# Microcontroller.net
KiCad netlist of a schematic drawn in Altium Designer
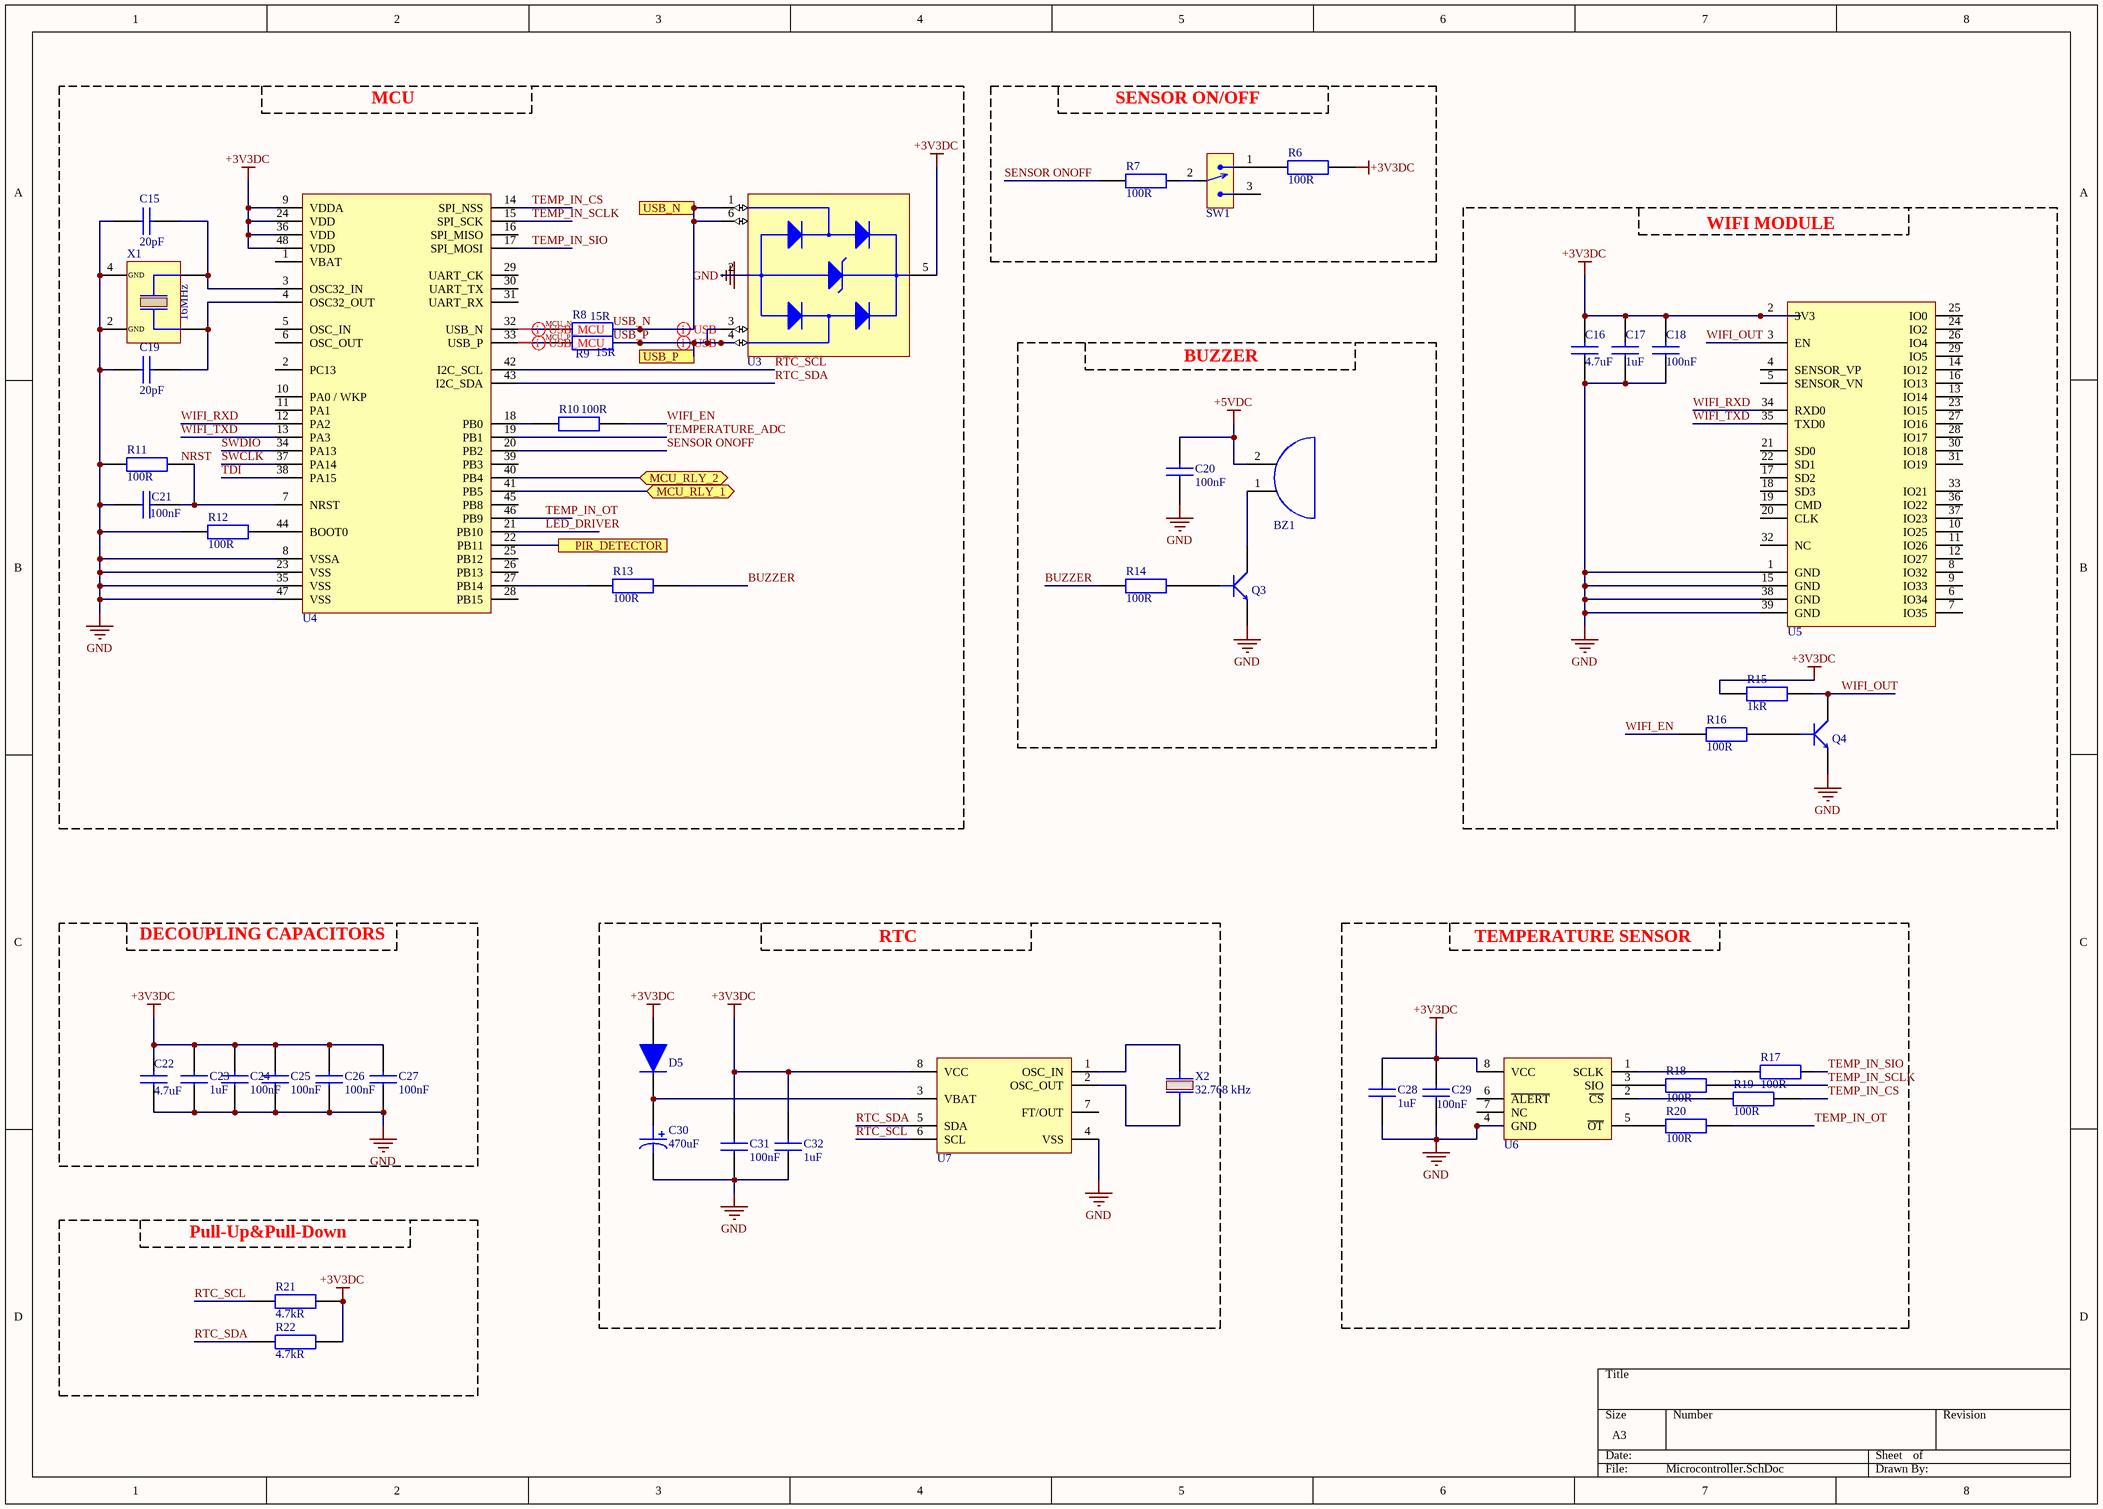
[diagram p0: Microcontroller.SchDoc]

(export (version "E")
  (design (tool "Eeschema 10.0.6"))
  (components
    (comp (ref "BZ1")
      (value "CMI-9605IC-0580T")
      (footprint "CMI-9605IC")
      (description "Buzzers Indicator, Internally Driven Magnetic 5V 30mA 2.7kHz 80dB @ 5V, 10cm Through Hole PC Pins")
      (fields (field (name "MANUFACTURER") "CUI Devices") (field (name "DESIGNED BY") "BERK"))
      (libsource (lib "UDEMY_Library") (part "CMI-9605IC-0580T"))
    )
    (comp (ref "C15")
      (value "CL10C200JB8NNNC")
      (footprint "CAP_0603")
      (description "CAP CER 20pF %5 0603 SMD")
      (fields
        (field (name "MANUFACTURER") "Samsung")
        (field (name "TOLERANCE") "5%")
        (field (name "CAPACITANCE") "20pF")
        (field (name "DESIGNED BY") "BERK")
      )
      (libsource (lib "UDEMY_Library") (part "CAP CER 20pF 0603"))
    )
    (comp (ref "C16")
      (value "CL21A475KAQNNNE")
      (footprint "CAP_0805")
      (description "CAP CER 4.7uF %10 0805")
      (fields
        (field (name "MANUFACTURER") "Samsung")
        (field (name "TOLERANCE") "10%")
        (field (name "CAPACITANCE") "4.7uF")
        (field (name "DESIGNED BY") "BERK")
      )
      (libsource (lib "UDEMY_Library") (part "CAP CER 4.7uF 0805"))
    )
    (comp (ref "C17")
      (value "CL21B105KBFNNNE")
      (footprint "CAP_0805")
      (description "CAP CER 1uF %10 0805")
      (fields
        (field (name "MANUFACTURER") "Samsung")
        (field (name "TOLERANCE") "10%")
        (field (name "CAPACITANCE") "1uF")
        (field (name "DESIGNED BY") "BERK")
      )
      (libsource (lib "UDEMY_Library") (part "CAP CER 1uF 0805"))
    )
    (comp (ref "C18")
      (value "CL21B104KBCNNNC")
      (footprint "CAP_0805")
      (description "CAP CER 100nF %10 0805")
      (fields
        (field (name "MANUFACTURER") "Samsung")
        (field (name "TOLERANCE") "10%")
        (field (name "CAPACITANCE") "100nF")
        (field (name "DESIGNED BY") "BERK")
      )
      (libsource (lib "UDEMY_Library") (part "CAP CER 100nF 0805"))
    )
    (comp (ref "C19")
      (value "CL10C200JB8NNNC")
      (footprint "CAP_0603")
      (description "CAP CER 20pF %5 0603 SMD")
      (fields
        (field (name "MANUFACTURER") "Samsung")
        (field (name "TOLERANCE") "5%")
        (field (name "CAPACITANCE") "20pF")
        (field (name "DESIGNED BY") "BERK")
      )
      (libsource (lib "UDEMY_Library") (part "CAP CER 20pF 0603"))
    )
    (comp (ref "C20")
      (value "CL21B104KBCNNNC")
      (footprint "CAP_0805")
      (description "CAP CER 100nF %10 0805")
      (fields
        (field (name "MANUFACTURER") "Samsung")
        (field (name "TOLERANCE") "10%")
        (field (name "CAPACITANCE") "100nF")
        (field (name "DESIGNED BY") "BERK")
      )
      (libsource (lib "UDEMY_Library") (part "CAP CER 100nF 0805"))
    )
    (comp (ref "C21")
      (value "C0603C104K5RACTU")
      (footprint "CAP_0603")
      (description "CAP CER 100nF %10 0603 SMD")
      (fields
        (field (name "MANUFACTURER") "KEMET")
        (field (name "TOLERANCE") "10%")
        (field (name "CAPACITANCE") "100nF")
        (field (name "DESIGNED BY") "BERK")
      )
      (libsource (lib "UDEMY_Library") (part "CAP CER 100nF 0603"))
    )
    (comp (ref "C22")
      (value "CL21A475KAQNNNE")
      (footprint "CAP_0805")
      (description "CAP CER 4.7uF %10 0805")
      (fields
        (field (name "MANUFACTURER") "Samsung")
        (field (name "TOLERANCE") "10%")
        (field (name "CAPACITANCE") "4.7uF")
        (field (name "DESIGNED BY") "BERK")
      )
      (libsource (lib "UDEMY_Library") (part "CAP CER 4.7uF 0805"))
    )
    (comp (ref "C23")
      (value "CL21B105KBFNNNE")
      (footprint "CAP_0805")
      (description "CAP CER 1uF %10 0805")
      (fields
        (field (name "MANUFACTURER") "Samsung")
        (field (name "TOLERANCE") "10%")
        (field (name "CAPACITANCE") "1uF")
        (field (name "DESIGNED BY") "BERK")
      )
      (libsource (lib "UDEMY_Library") (part "CAP CER 1uF 0805"))
    )
    (comp (ref "C24")
      (value "CL21B104KBCNNNC")
      (footprint "CAP_0805")
      (description "CAP CER 100nF %10 0805")
      (fields
        (field (name "MANUFACTURER") "Samsung")
        (field (name "TOLERANCE") "10%")
        (field (name "CAPACITANCE") "100nF")
        (field (name "DESIGNED BY") "BERK")
      )
      (libsource (lib "UDEMY_Library") (part "CAP CER 100nF 0805"))
    )
    (comp (ref "C25")
      (value "CL21B104KBCNNNC")
      (footprint "CAP_0805")
      (description "CAP CER 100nF %10 0805")
      (fields
        (field (name "MANUFACTURER") "Samsung")
        (field (name "TOLERANCE") "10%")
        (field (name "CAPACITANCE") "100nF")
        (field (name "DESIGNED BY") "BERK")
      )
      (libsource (lib "UDEMY_Library") (part "CAP CER 100nF 0805"))
    )
    (comp (ref "C26")
      (value "CL21B104KBCNNNC")
      (footprint "CAP_0805")
      (description "CAP CER 100nF %10 0805")
      (fields
        (field (name "MANUFACTURER") "Samsung")
        (field (name "TOLERANCE") "10%")
        (field (name "CAPACITANCE") "100nF")
        (field (name "DESIGNED BY") "BERK")
      )
      (libsource (lib "UDEMY_Library") (part "CAP CER 100nF 0805"))
    )
    (comp (ref "C27")
      (value "CL21B104KBCNNNC")
      (footprint "CAP_0805")
      (description "CAP CER 100nF %10 0805")
      (fields
        (field (name "MANUFACTURER") "Samsung")
        (field (name "TOLERANCE") "10%")
        (field (name "CAPACITANCE") "100nF")
        (field (name "DESIGNED BY") "BERK")
      )
      (libsource (lib "UDEMY_Library") (part "CAP CER 100nF 0805"))
    )
    (comp (ref "C28")
      (value "CL21B105KBFNNNE")
      (footprint "CAP_0805")
      (description "CAP CER 1uF %10 0805")
      (fields
        (field (name "MANUFACTURER") "Samsung")
        (field (name "TOLERANCE") "10%")
        (field (name "CAPACITANCE") "1uF")
        (field (name "DESIGNED BY") "BERK")
      )
      (libsource (lib "UDEMY_Library") (part "CAP CER 1uF 0805"))
    )
    (comp (ref "C29")
      (value "CL21B104KBCNNNC")
      (footprint "CAP_0805")
      (description "CAP CER 100nF %10 0805")
      (fields
        (field (name "MANUFACTURER") "Samsung")
        (field (name "TOLERANCE") "10%")
        (field (name "CAPACITANCE") "100nF")
        (field (name "DESIGNED BY") "BERK")
      )
      (libsource (lib "UDEMY_Library") (part "CAP CER 100nF 0805"))
    )
    (comp (ref "C30")
      (value "ESH477M050AH4AA")
      (footprint "CAP_RADIAL_D10_P5")
      (description "CAP ALU ELEC 470uF 50V RADIAL")
      (fields
        (field (name "MANUFACTURER") "KEMET")
        (field (name "TOLERANCE") "20%")
        (field (name "CAPACITANCE") "470uF")
        (field (name "DESIGNED BY") "BERK")
      )
      (libsource (lib "UDEMY_Library") (part "CAP ALU ELEC 470uF 50V"))
    )
    (comp (ref "C31")
      (value "CL21B104KBCNNNC")
      (footprint "CAP_0805")
      (description "CAP CER 100nF %10 0805")
      (fields
        (field (name "MANUFACTURER") "Samsung")
        (field (name "TOLERANCE") "10%")
        (field (name "CAPACITANCE") "100nF")
        (field (name "DESIGNED BY") "BERK")
      )
      (libsource (lib "UDEMY_Library") (part "CAP CER 100nF 0805"))
    )
    (comp (ref "C32")
      (value "CL21B105KBFNNNE")
      (footprint "CAP_0805")
      (description "CAP CER 1uF %10 0805")
      (fields
        (field (name "MANUFACTURER") "Samsung")
        (field (name "TOLERANCE") "10%")
        (field (name "CAPACITANCE") "1uF")
        (field (name "DESIGNED BY") "BERK")
      )
      (libsource (lib "UDEMY_Library") (part "CAP CER 1uF 0805"))
    )
    (comp (ref "D5")
      (value "1N4148WS")
      (footprint "SOD323F")
      (description "Diode, Single, 75 V, 150 mA, 1 V, 4 ns")
      (fields
        (field (name "MANUFACTURER") "ON Semiconductor / Fairchild")
        (field (name "DESIGNED BY") "BERK")
      )
      (libsource (lib "UDEMY_Library") (part "1N4148WS"))
    )
    (comp (ref "Q3")
      (value "MMBT3904-7-F")
      (footprint "SOT-23F")
      (description "Transistor General Purpose BJT NPN 40 Volt 0.2A Automotive 3-Pin SOT-23")
      (fields (field (name "MANUFACTURER") "Diodes Zetex") (field (name "DESIGNED BY") "BERK"))
      (libsource (lib "UDEMY_Library") (part "MMBT3904-7-F"))
    )
    (comp (ref "Q4")
      (value "MMBT3904-7-F")
      (footprint "SOT-23F")
      (description "Transistor General Purpose BJT NPN 40 Volt 0.2A Automotive 3-Pin SOT-23")
      (fields (field (name "MANUFACTURER") "Diodes Zetex") (field (name "DESIGNED BY") "BERK"))
      (libsource (lib "UDEMY_Library") (part "MMBT3904-7-F"))
    )
    (comp (ref "R6")
      (value "RC0603JR-07100RL")
      (footprint "RES_0603")
      (description "RES 100 %5 OHM 0603 SMD")
      (fields
        (field (name "MANUFACTURER") "Yageo")
        (field (name "TOLERANCE") "5%")
        (field (name "RESISTANCE") "100R")
        (field (name "DESIGNED BY") "BERK")
      )
      (libsource (lib "UDEMY_Library") (part "RES 100 OHM 0603"))
    )
    (comp (ref "R7")
      (value "RC0603JR-07100RL")
      (footprint "RES_0603")
      (description "RES 100 %5 OHM 0603 SMD")
      (fields
        (field (name "MANUFACTURER") "Yageo")
        (field (name "TOLERANCE") "5%")
        (field (name "RESISTANCE") "100R")
        (field (name "DESIGNED BY") "BERK")
      )
      (libsource (lib "UDEMY_Library") (part "RES 100 OHM 0603"))
    )
    (comp (ref "R8")
      (value "RC0603JR-0715RL")
      (footprint "RES_0603")
      (description "RES 15 %5 OHM 0603 SMD")
      (fields
        (field (name "MANUFACTURER") "Yageo")
        (field (name "TOLERANCE") "5%")
        (field (name "RESISTANCE") "15R")
        (field (name "DESIGNED BY") "BERK")
      )
      (libsource (lib "UDEMY_Library") (part "RES 15 OHM 0603"))
    )
    (comp (ref "R9")
      (value "RC0603JR-0715RL")
      (footprint "RES_0603")
      (description "RES 15 %5 OHM 0603 SMD")
      (fields
        (field (name "MANUFACTURER") "Yageo")
        (field (name "TOLERANCE") "5%")
        (field (name "RESISTANCE") "15R")
        (field (name "DESIGNED BY") "BERK")
      )
      (libsource (lib "UDEMY_Library") (part "RES 15 OHM 0603"))
    )
    (comp (ref "R10")
      (value "RC0603JR-07100RL")
      (footprint "RES_0603")
      (description "RES 100 %5 OHM 0603 SMD")
      (fields
        (field (name "MANUFACTURER") "Yageo")
        (field (name "TOLERANCE") "5%")
        (field (name "RESISTANCE") "100R")
        (field (name "DESIGNED BY") "BERK")
      )
      (libsource (lib "UDEMY_Library") (part "RES 100 OHM 0603"))
    )
    (comp (ref "R11")
      (value "RC0603JR-07100RL")
      (footprint "RES_0603")
      (description "RES 100 %5 OHM 0603 SMD")
      (fields
        (field (name "MANUFACTURER") "Yageo")
        (field (name "TOLERANCE") "5%")
        (field (name "RESISTANCE") "100R")
        (field (name "DESIGNED BY") "BERK")
      )
      (libsource (lib "UDEMY_Library") (part "RES 100 OHM 0603"))
    )
    (comp (ref "R12")
      (value "RC0603JR-07100RL")
      (footprint "RES_0603")
      (description "RES 100 %5 OHM 0603 SMD")
      (fields
        (field (name "MANUFACTURER") "Yageo")
        (field (name "TOLERANCE") "5%")
        (field (name "RESISTANCE") "100R")
        (field (name "DESIGNED BY") "BERK")
      )
      (libsource (lib "UDEMY_Library") (part "RES 100 OHM 0603"))
    )
    (comp (ref "R13")
      (value "RC0603JR-07100RL")
      (footprint "RES_0603")
      (description "RES 100 %5 OHM 0603 SMD")
      (fields
        (field (name "MANUFACTURER") "Yageo")
        (field (name "TOLERANCE") "5%")
        (field (name "RESISTANCE") "100R")
        (field (name "DESIGNED BY") "BERK")
      )
      (libsource (lib "UDEMY_Library") (part "RES 100 OHM 0603"))
    )
    (comp (ref "R14")
      (value "RC0603JR-07100RL")
      (footprint "RES_0603")
      (description "RES 100 %5 OHM 0603 SMD")
      (fields
        (field (name "MANUFACTURER") "Yageo")
        (field (name "TOLERANCE") "5%")
        (field (name "RESISTANCE") "100R")
        (field (name "DESIGNED BY") "BERK")
      )
      (libsource (lib "") (part "RES 100 OHM 0603_1"))
    )
    (comp (ref "R15")
      (value "RC0603FR-0710KL")
      (footprint "RES_0603")
      (description "RES 1K %1 OHM 0603 SMD")
      (fields
        (field (name "MANUFACTURER") "Yageo")
        (field (name "MANUFACTURER PART NUMBER") "RC0603JR-071KL")
        (field (name "RESISTANCE") "1kR")
        (field (name "DESIGNED BY") "BERK")
      )
      (libsource (lib "UDEMY_Library") (part "RES 1K OHM 0603"))
    )
    (comp (ref "R16")
      (value "RC0603JR-07100RL")
      (footprint "RES_0603")
      (description "RES 100 %5 OHM 0603 SMD")
      (fields
        (field (name "MANUFACTURER") "Yageo")
        (field (name "TOLERANCE") "5%")
        (field (name "RESISTANCE") "100R")
        (field (name "DESIGNED BY") "BERK")
      )
      (libsource (lib "") (part "RES 100 OHM 0603_1"))
    )
    (comp (ref "R17")
      (value "RC0603JR-07100RL")
      (footprint "RES_0603")
      (description "RES 100 %5 OHM 0603 SMD")
      (fields
        (field (name "MANUFACTURER") "Yageo")
        (field (name "TOLERANCE") "5%")
        (field (name "RESISTANCE") "100R")
        (field (name "DESIGNED BY") "BERK")
      )
      (libsource (lib "UDEMY_Library") (part "RES 100 OHM 0603"))
    )
    (comp (ref "R18")
      (value "RC0603JR-07100RL")
      (footprint "RES_0603")
      (description "RES 100 %5 OHM 0603 SMD")
      (fields
        (field (name "MANUFACTURER") "Yageo")
        (field (name "TOLERANCE") "5%")
        (field (name "RESISTANCE") "100R")
        (field (name "DESIGNED BY") "BERK")
      )
      (libsource (lib "UDEMY_Library") (part "RES 100 OHM 0603"))
    )
    (comp (ref "R19")
      (value "RC0603JR-07100RL")
      (footprint "RES_0603")
      (description "RES 100 %5 OHM 0603 SMD")
      (fields
        (field (name "MANUFACTURER") "Yageo")
        (field (name "TOLERANCE") "5%")
        (field (name "RESISTANCE") "100R")
        (field (name "DESIGNED BY") "BERK")
      )
      (libsource (lib "UDEMY_Library") (part "RES 100 OHM 0603"))
    )
    (comp (ref "R20")
      (value "RC0603JR-07100RL")
      (footprint "RES_0603")
      (description "RES 100 %5 OHM 0603 SMD")
      (fields
        (field (name "MANUFACTURER") "Yageo")
        (field (name "TOLERANCE") "5%")
        (field (name "RESISTANCE") "100R")
        (field (name "DESIGNED BY") "BERK")
      )
      (libsource (lib "") (part "RES 100 OHM 0603_1"))
    )
    (comp (ref "R21")
      (value "RC0603JR-074K7L")
      (footprint "RES_0603")
      (description "RES 4K7 %5 OHM 0603 SMD")
      (fields
        (field (name "MANUFACTURER") "Yageo")
        (field (name "TOLERANCE") "5%")
        (field (name "RESISTANCE") "4.7kR")
        (field (name "DESIGNED BY") "BERK")
      )
      (libsource (lib "UDEMY_Library") (part "RES 4K7 OHM 0603"))
    )
    (comp (ref "R22")
      (value "RC0603JR-074K7L")
      (footprint "RES_0603")
      (description "RES 4K7 %5 OHM 0603 SMD")
      (fields
        (field (name "MANUFACTURER") "Yageo")
        (field (name "TOLERANCE") "5%")
        (field (name "RESISTANCE") "4.7kR")
        (field (name "DESIGNED BY") "BERK")
      )
      (libsource (lib "UDEMY_Library") (part "RES 4K7 OHM 0603"))
    )
    (comp (ref "SW1")
      (value "EG1215AA")
      (footprint "EG1215AA")
      (description "Slide Switch, SPDT, 0.025A, 24V, SMD")
      (fields
        (field (name "MANUFACTURER") "E-Switch")
        (field (name "TOLERANCE") "4.95%")
        (field (name "DESIGNED BY") "BERK")
      )
      (libsource (lib "UDEMY_Library") (part "EG1215AA"))
    )
    (comp (ref "U3")
      (value "USBLC6-2SC6")
      (footprint "SOT23-6L")
      (description "TVS DIODE 5.25V 17V SOT23-6")
      (fields (field (name "MANUFACTURER") "STMicroelectronics") (field (name "DESIGNED BY") "BERK"))
      (libsource (lib "UDEMY_Library") (part "USB PROTECTION"))
    )
    (comp (ref "U4")
      (value "STM32F103C6T6A")
      (footprint "LQFP-48")
      (description "MCU 32-bit STM32F ARM Cortex M3 RISC 32KB Flash 2.5V/3.3V 48-Pin LQFP Tray")
      (fields (field (name "MANUFACTURER") "STMicroelectronics") (field (name "DESIGNED BY") "BERK"))
      (libsource (lib "UDEMY_Library") (part "STM32F103C6T6A"))
    )
    (comp (ref "U5")
      (value "ESP32-WROOM-32")
      (footprint "ESP32-32")
      (description "SMD MODULE, ESP32-D0WDQ6, 32MBIT")
      (fields (field (name "MANUFACTURER") "Espressif Systems") (field (name "DESIGNED BY") "BERK"))
      (libsource (lib "UDEMY_Library") (part "ESP32-WROOM-32"))
    )
    (comp (ref "U6")
      (value "MAX6662")
      (footprint "SOIC8")
      (description "SENSOR TEMPERATURE SPI 8SOIC")
      (fields
        (field (name "MANUFACTURER") "Maxim")
        (field (name "MANUFACTURER PART NUMBER") "MAX6662MSA+")
        (field (name "DESIGNED BY") "BERK")
      )
      (libsource (lib "UDEMY_Library") (part "MAX6662"))
    )
    (comp (ref "U7")
      (value "M41T00M6F")
      (footprint "SOIC8")
      (description "IC RTC CLK/CALENDAR I2C 8-SOIC")
      (fields (field (name "MANUFACTURER") "STMicroelectronics") (field (name "DESIGNED BY") "BERK"))
      (libsource (lib "UDEMY_Library") (part "M41T00M6F"))
    )
    (comp (ref "X1")
      (value "ECS-160-20-30B-TR")
      (footprint "ECS")
      (description "CRYSTAL 16.0000MHZ 20PF SMD")
      (fields
        (field (name "MANUFACTURER") "ECS International")
        (field (name "TOLERANCE") "50ppm")
        (field (name "FREQUENCY") "16MHz")
        (field (name "DESIGNED BY") "BERK")
      )
      (libsource (lib "UDEMY_Library") (part "CRYSTAL 16MHz"))
    )
    (comp (ref "X2")
      (value "ABS05-32.768KHZ-T")
      (footprint "ABS05")
      (description "Crystal, 32.768 kHz, SMD, 1.6mm x 1mm, 12.5 pF, 20 ppm, ABS05 Series")
      (fields
        (field (name "MANUFACTURER") "Abracon")
        (field (name "TOLERANCE") "20ppm")
        (field (name "OPERATING FREQUENCY") "32.768 kHz")
        (field (name "DESIGNED BY") "BERK")
      )
      (libsource (lib "UDEMY_Library") (part "CRYSTAL 32768kHZ"))
    )
  )
  (nets
    (net (code "1") (name "+3V3DC") (class "Default")
      (node (ref "C16") (pin "2") (pinfunction "2_2") (pintype "passive"))
      (node (ref "C17") (pin "2") (pinfunction "2_2") (pintype "passive"))
      (node (ref "C18") (pin "2") (pinfunction "2_2") (pintype "passive"))
      (node (ref "C22") (pin "2") (pinfunction "2_2") (pintype "passive"))
      (node (ref "C23") (pin "2") (pinfunction "2_2") (pintype "passive"))
      (node (ref "C24") (pin "2") (pinfunction "2_2") (pintype "passive"))
      (node (ref "C25") (pin "2") (pinfunction "2_2") (pintype "passive"))
      (node (ref "C26") (pin "2") (pinfunction "2_2") (pintype "passive"))
      (node (ref "C27") (pin "2") (pinfunction "2_2") (pintype "passive"))
      (node (ref "C28") (pin "2") (pinfunction "2_2") (pintype "passive"))
      (node (ref "C29") (pin "2") (pinfunction "2_2") (pintype "passive"))
      (node (ref "C31") (pin "2") (pinfunction "2_2") (pintype "passive"))
      (node (ref "C32") (pin "2") (pinfunction "2_2") (pintype "passive"))
      (node (ref "D5") (pin "2") (pinfunction "2_2") (pintype "power_in"))
      (node (ref "R15") (pin "1") (pinfunction "1_1") (pintype "passive"))
      (node (ref "R21") (pin "2") (pinfunction "2_2") (pintype "passive"))
      (node (ref "R22") (pin "2") (pinfunction "2_2") (pintype "passive"))
      (node (ref "R6") (pin "2") (pinfunction "2_2") (pintype "passive"))
      (node (ref "U3") (pin "5") (pinfunction "VBUS_5") (pintype "power_in"))
      (node (ref "U4") (pin "24") (pinfunction "VDD_24") (pintype "passive"))
      (node (ref "U4") (pin "36") (pinfunction "VDD_36") (pintype "passive"))
      (node (ref "U4") (pin "48") (pinfunction "VDD_48") (pintype "passive"))
      (node (ref "U4") (pin "9") (pinfunction "VDDA_9") (pintype "passive"))
      (node (ref "U5") (pin "2") (pinfunction "3V3_2") (pintype "passive"))
      (node (ref "U6") (pin "8") (pinfunction "VCC_8") (pintype "passive"))
      (node (ref "U7") (pin "8") (pinfunction "VCC_8") (pintype "passive"))
    )
    (net (code "2") (name "+5VDC") (class "Default")
      (node (ref "BZ1") (pin "2") (pinfunction "2_2") (pintype "passive"))
      (node (ref "C20") (pin "2") (pinfunction "2_2") (pintype "passive"))
    )
    (net (code "3") (name "/BUZZER") (class "Default")
      (node (ref "R13") (pin "2") (pinfunction "2_2") (pintype "passive"))
      (node (ref "R14") (pin "2") (pinfunction "2_2") (pintype "passive"))
    )
    (net (code "4") (name "/LED_DRIVER") (class "Default")
      (node (ref "U4") (pin "21") (pinfunction "PB10_21") (pintype "passive"))
    )
    (net (code "5") (name "/MCU_N") (class "Default")
      (node (ref "R8") (pin "1") (pinfunction "1_1") (pintype "passive"))
      (node (ref "U4") (pin "32") (pinfunction "USB_N_32") (pintype "passive"))
    )
    (net (code "6") (name "/MCU_P") (class "Default")
      (node (ref "R9") (pin "1") (pinfunction "1_1") (pintype "passive"))
      (node (ref "U4") (pin "33") (pinfunction "USB_P_33") (pintype "passive"))
    )
    (net (code "7") (name "/MCU_RLY_1") (class "Default")
      (node (ref "U4") (pin "41") (pinfunction "PB5_41") (pintype "passive"))
    )
    (net (code "8") (name "/MCU_RLY_2") (class "Default")
      (node (ref "U4") (pin "40") (pinfunction "PB4_40") (pintype "passive"))
    )
    (net (code "10") (name "/PIR_DETECTOR") (class "Default")
      (node (ref "U4") (pin "22") (pinfunction "PB11_22") (pintype "passive"))
    )
    (net (code "11") (name "/RTC_SCL") (class "Default")
      (node (ref "R21") (pin "1") (pinfunction "1_1") (pintype "passive"))
      (node (ref "U4") (pin "42") (pinfunction "I2C_SCL_42") (pintype "passive"))
      (node (ref "U7") (pin "6") (pinfunction "SCL_6") (pintype "passive"))
    )
    (net (code "12") (name "/RTC_SDA") (class "Default")
      (node (ref "R22") (pin "1") (pinfunction "1_1") (pintype "passive"))
      (node (ref "U4") (pin "43") (pinfunction "I2C_SDA_43") (pintype "passive"))
      (node (ref "U7") (pin "5") (pinfunction "SDA_5") (pintype "passive"))
    )
    (net (code "13") (name "/SENSOR ONOFF") (class "Default")
      (node (ref "R7") (pin "1") (pinfunction "1_1") (pintype "passive"))
      (node (ref "U4") (pin "20") (pinfunction "PB2_20") (pintype "passive"))
    )
    (net (code "14") (name "/SWCLK") (class "Default")
      (node (ref "U4") (pin "37") (pinfunction "PA14_37") (pintype "passive"))
    )
    (net (code "15") (name "/SWDIO") (class "Default")
      (node (ref "U4") (pin "34") (pinfunction "PA13_34") (pintype "passive"))
    )
    (net (code "16") (name "/TDI") (class "Default")
      (node (ref "U4") (pin "38") (pinfunction "PA15_38") (pintype "passive"))
    )
    (net (code "17") (name "/TEMPERATURE_ADC") (class "Default")
      (node (ref "U4") (pin "19") (pinfunction "PB1_19") (pintype "passive"))
    )
    (net (code "18") (name "/TEMP_IN_CS") (class "Default")
      (node (ref "R19") (pin "2") (pinfunction "2_2") (pintype "passive"))
      (node (ref "U4") (pin "14") (pinfunction "SPI_NSS_14") (pintype "passive"))
    )
    (net (code "19") (name "/TEMP_IN_OT") (class "Default")
      (node (ref "R20") (pin "1") (pinfunction "1_1") (pintype "passive"))
      (node (ref "U4") (pin "46") (pinfunction "PB9_46") (pintype "passive"))
    )
    (net (code "20") (name "/TEMP_IN_SCLK") (class "Default")
      (node (ref "R18") (pin "2") (pinfunction "2_2") (pintype "passive"))
      (node (ref "U4") (pin "15") (pinfunction "SPI_SCK_15") (pintype "passive"))
    )
    (net (code "21") (name "/TEMP_IN_SIO") (class "Default")
      (node (ref "R17") (pin "2") (pinfunction "2_2") (pintype "passive"))
      (node (ref "U4") (pin "17") (pinfunction "SPI_MOSI_17") (pintype "passive"))
    )
    (net (code "22") (name "/USB_N") (class "Default")
      (node (ref "R8") (pin "2") (pinfunction "2_2") (pintype "passive"))
      (node (ref "U3") (pin "1") (pinfunction "I/O1_1") (pintype "bidirectional"))
      (node (ref "U3") (pin "6") (pinfunction "I/O1_6") (pintype "bidirectional"))
    )
    (net (code "23") (name "/USB_P") (class "Default")
      (node (ref "R9") (pin "2") (pinfunction "2_2") (pintype "passive"))
      (node (ref "U3") (pin "3") (pinfunction "I/O2_3") (pintype "bidirectional"))
      (node (ref "U3") (pin "4") (pinfunction "I/O2_4") (pintype "bidirectional"))
    )
    (net (code "24") (name "/WIFI_EN") (class "Default")
      (node (ref "R10") (pin "2") (pinfunction "2_2") (pintype "passive"))
      (node (ref "R16") (pin "2") (pinfunction "2_2") (pintype "passive"))
    )
    (net (code "25") (name "/WIFI_OUT") (class "Default")
      (node (ref "Q4") (pin "3") (pinfunction "C_3") (pintype "power_in"))
      (node (ref "R15") (pin "2") (pinfunction "2_2") (pintype "passive"))
      (node (ref "U5") (pin "3") (pinfunction "EN_3") (pintype "passive"))
    )
    (net (code "26") (name "/WIFI_RXD") (class "Default")
      (node (ref "U4") (pin "12") (pinfunction "PA2_12") (pintype "passive"))
      (node (ref "U5") (pin "34") (pinfunction "RXD0_34") (pintype "passive"))
    )
    (net (code "27") (name "/WIFI_TXD") (class "Default")
      (node (ref "U4") (pin "13") (pinfunction "PA3_13") (pintype "passive"))
      (node (ref "U5") (pin "35") (pinfunction "TXD0_35") (pintype "passive"))
    )
    (net (code "28") (name "GND") (class "Default")
      (node (ref "C15") (pin "1") (pinfunction "1_1") (pintype "passive"))
      (node (ref "C16") (pin "1") (pinfunction "1_1") (pintype "passive"))
      (node (ref "C17") (pin "1") (pinfunction "1_1") (pintype "passive"))
      (node (ref "C18") (pin "1") (pinfunction "1_1") (pintype "passive"))
      (node (ref "C19") (pin "1") (pinfunction "1_1") (pintype "passive"))
      (node (ref "C20") (pin "1") (pinfunction "1_1") (pintype "passive"))
      (node (ref "C21") (pin "1") (pinfunction "1_1") (pintype "passive"))
      (node (ref "C22") (pin "1") (pinfunction "1_1") (pintype "passive"))
      (node (ref "C23") (pin "1") (pinfunction "1_1") (pintype "passive"))
      (node (ref "C24") (pin "1") (pinfunction "1_1") (pintype "passive"))
      (node (ref "C25") (pin "1") (pinfunction "1_1") (pintype "passive"))
      (node (ref "C26") (pin "1") (pinfunction "1_1") (pintype "passive"))
      (node (ref "C27") (pin "1") (pinfunction "1_1") (pintype "passive"))
      (node (ref "C28") (pin "1") (pinfunction "1_1") (pintype "passive"))
      (node (ref "C29") (pin "1") (pinfunction "1_1") (pintype "passive"))
      (node (ref "C30") (pin "2") (pinfunction "2_2") (pintype "passive"))
      (node (ref "C31") (pin "1") (pinfunction "1_1") (pintype "passive"))
      (node (ref "C32") (pin "1") (pinfunction "1_1") (pintype "passive"))
      (node (ref "Q3") (pin "2") (pinfunction "E_2") (pintype "power_in"))
      (node (ref "Q4") (pin "2") (pinfunction "E_2") (pintype "power_in"))
      (node (ref "R11") (pin "1") (pinfunction "1_1") (pintype "passive"))
      (node (ref "R12") (pin "1") (pinfunction "1_1") (pintype "passive"))
      (node (ref "U3") (pin "2") (pinfunction "GND_2") (pintype "power_in"))
      (node (ref "U4") (pin "23") (pinfunction "VSS_23") (pintype "passive"))
      (node (ref "U4") (pin "35") (pinfunction "VSS_35") (pintype "passive"))
      (node (ref "U4") (pin "47") (pinfunction "VSS_47") (pintype "passive"))
      (node (ref "U4") (pin "8") (pinfunction "VSSA_8") (pintype "passive"))
      (node (ref "U5") (pin "1") (pinfunction "GND_1") (pintype "passive"))
      (node (ref "U5") (pin "15") (pinfunction "GND_15") (pintype "passive"))
      (node (ref "U5") (pin "38") (pinfunction "GND_38") (pintype "passive"))
      (node (ref "U5") (pin "39") (pinfunction "GND_39") (pintype "passive"))
      (node (ref "U6") (pin "4") (pinfunction "GND_4") (pintype "passive"))
      (node (ref "U7") (pin "4") (pinfunction "VSS_4") (pintype "passive"))
      (node (ref "X1") (pin "2") (pinfunction "GND_2") (pintype "passive"))
      (node (ref "X1") (pin "4") (pinfunction "GND_4") (pintype "passive"))
    )
    (net (code "29") (name "Net-(Q3-B)") (class "Default")
      (node (ref "Q3") (pin "1") (pinfunction "B_1") (pintype "power_in"))
      (node (ref "R14") (pin "1") (pinfunction "1_1") (pintype "passive"))
    )
    (net (code "30") (name "Net-(Q3-C)") (class "Default")
      (node (ref "BZ1") (pin "1") (pinfunction "1_1") (pintype "passive"))
      (node (ref "Q3") (pin "3") (pinfunction "C_3") (pintype "power_in"))
    )
    (net (code "31") (name "Net-(Q4-B)") (class "Default")
      (node (ref "Q4") (pin "1") (pinfunction "B_1") (pintype "power_in"))
      (node (ref "R16") (pin "1") (pinfunction "1_1") (pintype "passive"))
    )
    (net (code "32") (name "Net-(R6-Pad1)") (class "Default")
      (node (ref "R6") (pin "1") (pinfunction "1_1") (pintype "passive"))
      (node (ref "SW1") (pin "1") (pinfunction "1_1") (pintype "passive"))
    )
    (net (code "33") (name "Net-(R7-Pad2)") (class "Default")
      (node (ref "R7") (pin "2") (pinfunction "2_2") (pintype "passive"))
      (node (ref "SW1") (pin "2") (pinfunction "2_2") (pintype "passive"))
    )
    (net (code "34") (name "Net-(U4-BOOT0)") (class "Default")
      (node (ref "R12") (pin "2") (pinfunction "2_2") (pintype "passive"))
      (node (ref "U4") (pin "44") (pinfunction "BOOT0_44") (pintype "passive"))
    )
    (net (code "35") (name "Net-(U4-NRST)") (class "Default")
      (node (ref "C21") (pin "2") (pinfunction "2_2") (pintype "passive"))
      (node (ref "R11") (pin "2") (pinfunction "2_2") (pintype "passive"))
      (node (ref "U4") (pin "7") (pinfunction "NRST_7") (pintype "passive"))
    )
    (net (code "36") (name "Net-(U4-OSC32_IN)") (class "Default")
      (node (ref "C15") (pin "2") (pinfunction "2_2") (pintype "passive"))
      (node (ref "U4") (pin "3") (pinfunction "OSC32_IN_3") (pintype "passive"))
      (node (ref "X1") (pin "3") (pinfunction "3_3") (pintype "passive"))
    )
    (net (code "37") (name "Net-(U4-OSC32_OUT)") (class "Default")
      (node (ref "C19") (pin "2") (pinfunction "2_2") (pintype "passive"))
      (node (ref "U4") (pin "4") (pinfunction "OSC32_OUT_4") (pintype "passive"))
      (node (ref "X1") (pin "1") (pinfunction "1_1") (pintype "passive"))
    )
    (net (code "38") (name "Net-(U4-PB0)") (class "Default")
      (node (ref "R10") (pin "1") (pinfunction "1_1") (pintype "passive"))
      (node (ref "U4") (pin "18") (pinfunction "PB0_18") (pintype "passive"))
    )
    (net (code "39") (name "Net-(U4-PB14)") (class "Default")
      (node (ref "R13") (pin "1") (pinfunction "1_1") (pintype "passive"))
      (node (ref "U4") (pin "27") (pinfunction "PB14_27") (pintype "passive"))
    )
    (net (code "40") (name "Net-(U6-SCLK)") (class "Default")
      (node (ref "R17") (pin "1") (pinfunction "1_1") (pintype "passive"))
      (node (ref "U6") (pin "1") (pinfunction "SCLK_1") (pintype "passive"))
    )
    (net (code "41") (name "Net-(U6-SIO)") (class "Default")
      (node (ref "R18") (pin "1") (pinfunction "1_1") (pintype "passive"))
      (node (ref "U6") (pin "3") (pinfunction "SIO_3") (pintype "passive"))
    )
    (net (code "42") (name "Net-(U6-~{CS})") (class "Default")
      (node (ref "R19") (pin "1") (pinfunction "1_1") (pintype "passive"))
      (node (ref "U6") (pin "2") (pinfunction "~{CS}_2") (pintype "passive"))
    )
    (net (code "43") (name "Net-(U6-~{OT})") (class "Default")
      (node (ref "R20") (pin "2") (pinfunction "2_2") (pintype "passive"))
      (node (ref "U6") (pin "5") (pinfunction "~{OT}_5") (pintype "passive"))
    )
    (net (code "44") (name "Net-(U7-OSC_IN)") (class "Default")
      (node (ref "U7") (pin "1") (pinfunction "OSC_IN_1") (pintype "passive"))
      (node (ref "X2") (pin "2") (pinfunction "2_2") (pintype "passive"))
    )
    (net (code "45") (name "Net-(U7-OSC_OUT)") (class "Default")
      (node (ref "U7") (pin "2") (pinfunction "OSC_OUT_2") (pintype "passive"))
      (node (ref "X2") (pin "1") (pinfunction "1_1") (pintype "passive"))
    )
    (net (code "46") (name "Net-(U7-VBAT)") (class "Default")
      (node (ref "C30") (pin "1") (pinfunction "1_1") (pintype "passive"))
      (node (ref "D5") (pin "1") (pinfunction "1_1") (pintype "power_in"))
      (node (ref "U7") (pin "3") (pinfunction "VBAT_3") (pintype "passive"))
    )
    (net (code "47") (name "unconnected-(SW1-Pad3)") (class "Default")
      (node (ref "SW1") (pin "3") (pinfunction "3_3") (pintype "passive"))
    )
    (net (code "48") (name "unconnected-(U4-OSC_IN-Pad5)") (class "Default")
      (node (ref "U4") (pin "5") (pinfunction "OSC_IN_5") (pintype "passive"))
    )
    (net (code "49") (name "unconnected-(U4-OSC_OUT-Pad6)") (class "Default")
      (node (ref "U4") (pin "6") (pinfunction "OSC_OUT_6") (pintype "passive"))
    )
    (net (code "50") (name "unconnected-(U4-PA0_{slash}_WKP-Pad10)") (class "Default")
      (node (ref "U4") (pin "10") (pinfunction "PA0_/_WKP_10") (pintype "passive"))
    )
    (net (code "51") (name "unconnected-(U4-PA1-Pad11)") (class "Default")
      (node (ref "U4") (pin "11") (pinfunction "PA1_11") (pintype "passive"))
    )
    (net (code "52") (name "unconnected-(U4-PB3-Pad39)") (class "Default")
      (node (ref "U4") (pin "39") (pinfunction "PB3_39") (pintype "passive"))
    )
    (net (code "53") (name "unconnected-(U4-PB8-Pad45)") (class "Default")
      (node (ref "U4") (pin "45") (pinfunction "PB8_45") (pintype "passive"))
    )
    (net (code "54") (name "unconnected-(U4-PB12-Pad25)") (class "Default")
      (node (ref "U4") (pin "25") (pinfunction "PB12_25") (pintype "passive"))
    )
    (net (code "55") (name "unconnected-(U4-PB13-Pad26)") (class "Default")
      (node (ref "U4") (pin "26") (pinfunction "PB13_26") (pintype "passive"))
    )
    (net (code "56") (name "unconnected-(U4-PB15-Pad28)") (class "Default")
      (node (ref "U4") (pin "28") (pinfunction "PB15_28") (pintype "passive"))
    )
    (net (code "57") (name "unconnected-(U4-PC13-Pad2)") (class "Default")
      (node (ref "U4") (pin "2") (pinfunction "PC13_2") (pintype "passive"))
    )
    (net (code "58") (name "unconnected-(U4-SPI_MISO-Pad16)") (class "Default")
      (node (ref "U4") (pin "16") (pinfunction "SPI_MISO_16") (pintype "passive"))
    )
    (net (code "59") (name "unconnected-(U4-UART_CK-Pad29)") (class "Default")
      (node (ref "U4") (pin "29") (pinfunction "UART_CK_29") (pintype "passive"))
    )
    (net (code "60") (name "unconnected-(U4-UART_RX-Pad31)") (class "Default")
      (node (ref "U4") (pin "31") (pinfunction "UART_RX_31") (pintype "passive"))
    )
    (net (code "61") (name "unconnected-(U4-UART_TX-Pad30)") (class "Default")
      (node (ref "U4") (pin "30") (pinfunction "UART_TX_30") (pintype "passive"))
    )
    (net (code "62") (name "unconnected-(U4-VBAT-Pad1)") (class "Default")
      (node (ref "U4") (pin "1") (pinfunction "VBAT_1") (pintype "passive"))
    )
    (net (code "63") (name "unconnected-(U5-CLK-Pad20)") (class "Default")
      (node (ref "U5") (pin "20") (pinfunction "CLK_20") (pintype "passive"))
    )
    (net (code "64") (name "unconnected-(U5-CMD-Pad19)") (class "Default")
      (node (ref "U5") (pin "19") (pinfunction "CMD_19") (pintype "passive"))
    )
    (net (code "65") (name "unconnected-(U5-IO0-Pad25)") (class "Default")
      (node (ref "U5") (pin "25") (pinfunction "IO0_25") (pintype "passive"))
    )
    (net (code "66") (name "unconnected-(U5-IO2-Pad24)") (class "Default")
      (node (ref "U5") (pin "24") (pinfunction "IO2_24") (pintype "passive"))
    )
    (net (code "67") (name "unconnected-(U5-IO4-Pad26)") (class "Default")
      (node (ref "U5") (pin "26") (pinfunction "IO4_26") (pintype "passive"))
    )
    (net (code "68") (name "unconnected-(U5-IO5-Pad29)") (class "Default")
      (node (ref "U5") (pin "29") (pinfunction "IO5_29") (pintype "passive"))
    )
    (net (code "69") (name "unconnected-(U5-IO12-Pad14)") (class "Default")
      (node (ref "U5") (pin "14") (pinfunction "IO12_14") (pintype "passive"))
    )
    (net (code "70") (name "unconnected-(U5-IO13-Pad16)") (class "Default")
      (node (ref "U5") (pin "16") (pinfunction "IO13_16") (pintype "passive"))
    )
    (net (code "71") (name "unconnected-(U5-IO14-Pad13)") (class "Default")
      (node (ref "U5") (pin "13") (pinfunction "IO14_13") (pintype "passive"))
    )
    (net (code "72") (name "unconnected-(U5-IO15-Pad23)") (class "Default")
      (node (ref "U5") (pin "23") (pinfunction "IO15_23") (pintype "passive"))
    )
    (net (code "73") (name "unconnected-(U5-IO16-Pad27)") (class "Default")
      (node (ref "U5") (pin "27") (pinfunction "IO16_27") (pintype "passive"))
    )
    (net (code "74") (name "unconnected-(U5-IO17-Pad28)") (class "Default")
      (node (ref "U5") (pin "28") (pinfunction "IO17_28") (pintype "passive"))
    )
    (net (code "75") (name "unconnected-(U5-IO18-Pad30)") (class "Default")
      (node (ref "U5") (pin "30") (pinfunction "IO18_30") (pintype "passive"))
    )
    (net (code "76") (name "unconnected-(U5-IO19-Pad31)") (class "Default")
      (node (ref "U5") (pin "31") (pinfunction "IO19_31") (pintype "passive"))
    )
    (net (code "77") (name "unconnected-(U5-IO21-Pad33)") (class "Default")
      (node (ref "U5") (pin "33") (pinfunction "IO21_33") (pintype "passive"))
    )
    (net (code "78") (name "unconnected-(U5-IO22-Pad36)") (class "Default")
      (node (ref "U5") (pin "36") (pinfunction "IO22_36") (pintype "passive"))
    )
    (net (code "79") (name "unconnected-(U5-IO23-Pad37)") (class "Default")
      (node (ref "U5") (pin "37") (pinfunction "IO23_37") (pintype "passive"))
    )
    (net (code "80") (name "unconnected-(U5-IO25-Pad10)") (class "Default")
      (node (ref "U5") (pin "10") (pinfunction "IO25_10") (pintype "passive"))
    )
    (net (code "81") (name "unconnected-(U5-IO26-Pad11)") (class "Default")
      (node (ref "U5") (pin "11") (pinfunction "IO26_11") (pintype "passive"))
    )
    (net (code "82") (name "unconnected-(U5-IO27-Pad12)") (class "Default")
      (node (ref "U5") (pin "12") (pinfunction "IO27_12") (pintype "passive"))
    )
    (net (code "83") (name "unconnected-(U5-IO32-Pad8)") (class "Default")
      (node (ref "U5") (pin "8") (pinfunction "IO32_8") (pintype "passive"))
    )
    (net (code "84") (name "unconnected-(U5-IO33-Pad9)") (class "Default")
      (node (ref "U5") (pin "9") (pinfunction "IO33_9") (pintype "passive"))
    )
    (net (code "85") (name "unconnected-(U5-IO34-Pad6)") (class "Default")
      (node (ref "U5") (pin "6") (pinfunction "IO34_6") (pintype "passive"))
    )
    (net (code "86") (name "unconnected-(U5-IO35-Pad7)") (class "Default")
      (node (ref "U5") (pin "7") (pinfunction "IO35_7") (pintype "passive"))
    )
    (net (code "87") (name "unconnected-(U5-NC-Pad32)") (class "Default")
      (node (ref "U5") (pin "32") (pinfunction "NC_32") (pintype "passive"))
    )
    (net (code "88") (name "unconnected-(U5-SD0-Pad21)") (class "Default")
      (node (ref "U5") (pin "21") (pinfunction "SD0_21") (pintype "passive"))
    )
    (net (code "89") (name "unconnected-(U5-SD1-Pad22)") (class "Default")
      (node (ref "U5") (pin "22") (pinfunction "SD1_22") (pintype "passive"))
    )
    (net (code "90") (name "unconnected-(U5-SD2-Pad17)") (class "Default")
      (node (ref "U5") (pin "17") (pinfunction "SD2_17") (pintype "passive"))
    )
    (net (code "91") (name "unconnected-(U5-SD3-Pad18)") (class "Default")
      (node (ref "U5") (pin "18") (pinfunction "SD3_18") (pintype "passive"))
    )
    (net (code "92") (name "unconnected-(U5-SENSOR_VN-Pad5)") (class "Default")
      (node (ref "U5") (pin "5") (pinfunction "SENSOR_VN_5") (pintype "passive"))
    )
    (net (code "93") (name "unconnected-(U5-SENSOR_VP-Pad4)") (class "Default")
      (node (ref "U5") (pin "4") (pinfunction "SENSOR_VP_4") (pintype "passive"))
    )
    (net (code "94") (name "unconnected-(U6-NC-Pad7)") (class "Default")
      (node (ref "U6") (pin "7") (pinfunction "NC_7") (pintype "passive"))
    )
    (net (code "95") (name "unconnected-(U6-~{ALERT}-Pad6)") (class "Default")
      (node (ref "U6") (pin "6") (pinfunction "~{ALERT}_6") (pintype "passive"))
    )
    (net (code "96") (name "unconnected-(U7-FT{slash}OUT-Pad7)") (class "Default")
      (node (ref "U7") (pin "7") (pinfunction "FT/OUT_7") (pintype "passive"))
    )
  )
)
